# Spark-power-meter-main.net
KiCad netlist of a schematic drawn in EAGLE
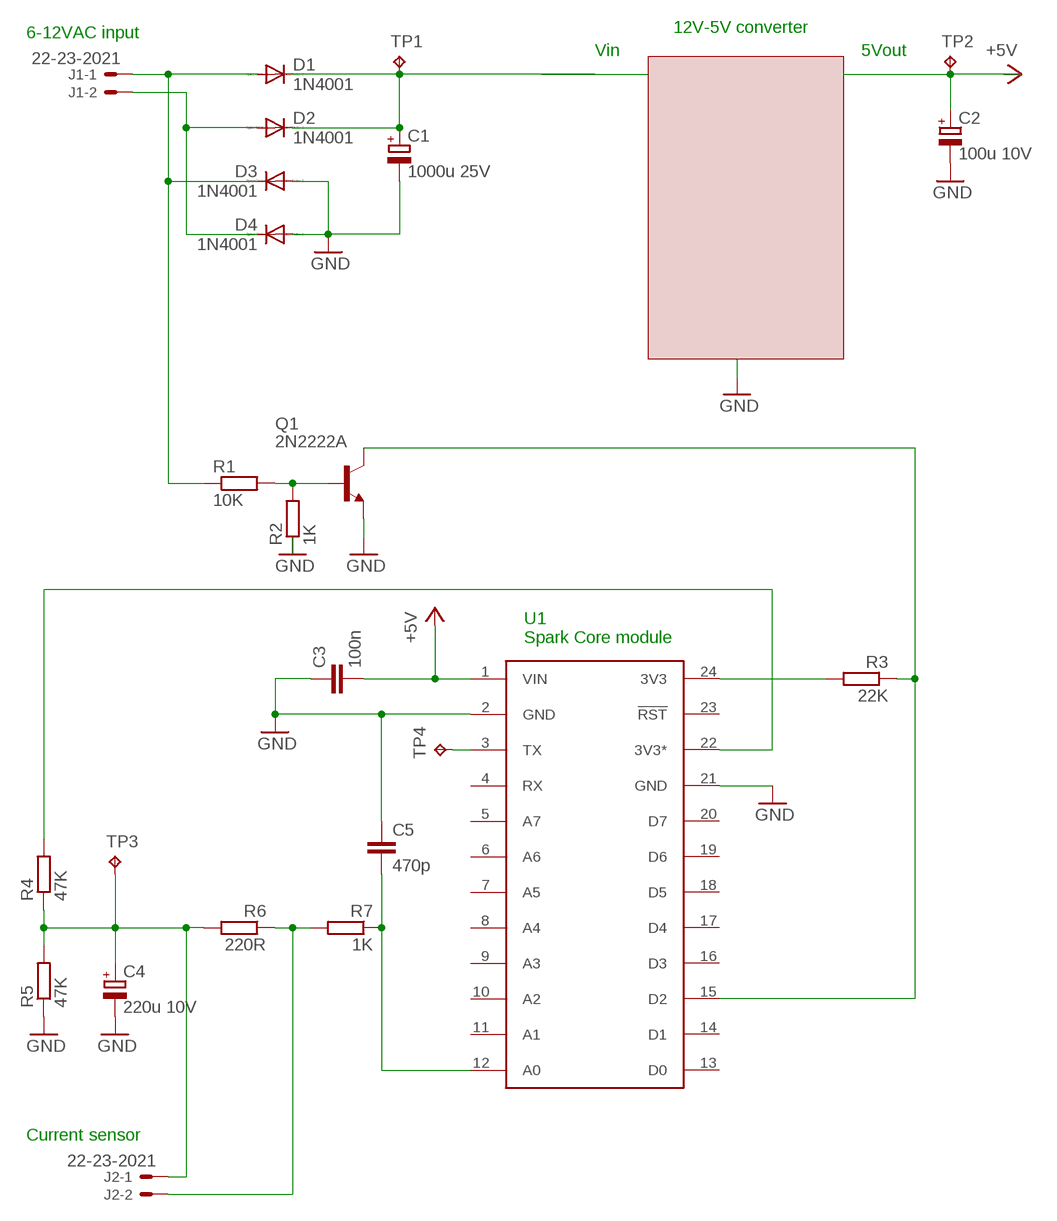
[diagram p0: schematic, sheet 1]

(export (version "E")
  (design (tool "Eeschema 10.0.6"))
  (components
    (comp (ref "C1")
      (value "1000u 25V")
      (footprint "eagle-import:E5R")
      (libsource (lib "eagle-import") (part "CPOL-EUE5-9VAXIAL"))
    )
    (comp (ref "C2")
      (value "100u 10V")
      (footprint "eagle-import:E5R")
      (libsource (lib "eagle-import") (part "CPOL-EUE5-9VAXIAL"))
    )
    (comp (ref "C3")
      (value "100n")
      (footprint "eagle-import:C075-032X103")
      (libsource (lib "eagle-import") (part "C-EU075-032X103"))
    )
    (comp (ref "C4")
      (value "220u 10V")
      (footprint "eagle-import:E5R")
      (libsource (lib "eagle-import") (part "CPOL-EUE5-9VAXIAL"))
    )
    (comp (ref "C5")
      (value "470p")
      (footprint "eagle-import:C075-032X103")
      (libsource (lib "eagle-import") (part "C-EU075-032X103"))
    )
    (comp (ref "D1")
      (value "1N4001")
      (footprint "eagle-import:DO41-10")
      (libsource (lib "eagle-import") (part "1N4004"))
    )
    (comp (ref "D2")
      (value "1N4001")
      (footprint "eagle-import:DO41-10")
      (libsource (lib "eagle-import") (part "1N4004"))
    )
    (comp (ref "D3")
      (value "1N4001")
      (footprint "eagle-import:DO41-10")
      (libsource (lib "eagle-import") (part "1N4004"))
    )
    (comp (ref "D4")
      (value "1N4001")
      (footprint "eagle-import:DO41-10")
      (libsource (lib "eagle-import") (part "1N4004"))
    )
    (comp (ref "J1")
      (value "22-23-2021")
      (footprint "eagle-import:22-23-2021")
      (fields (field (name "MF") "MOLEX"))
      (libsource (lib "eagle-import") (part "22-23-2021"))
    )
    (comp (ref "J2")
      (value "22-23-2021")
      (footprint "eagle-import:22-23-2021")
      (fields (field (name "MF") "MOLEX"))
      (libsource (lib "eagle-import") (part "22-23-2021"))
    )
    (comp (ref "Q1")
      (value "2N2222A")
      (footprint "eagle-import:TO18")
      (libsource (lib "eagle-import") (part "2N2222A"))
    )
    (comp (ref "R1")
      (value "10K")
      (footprint "eagle-import:0207_10")
      (libsource (lib "eagle-import") (part "R-EU_0207/10"))
    )
    (comp (ref "R2")
      (value "1K")
      (footprint "eagle-import:0207_10")
      (libsource (lib "eagle-import") (part "R-EU_0207/10"))
    )
    (comp (ref "R3")
      (value "22K")
      (footprint "eagle-import:0207_10")
      (libsource (lib "eagle-import") (part "R-EU_0207/10"))
    )
    (comp (ref "R4")
      (value "47K")
      (footprint "eagle-import:0207_10")
      (libsource (lib "eagle-import") (part "R-EU_0207/10"))
    )
    (comp (ref "R5")
      (value "47K")
      (footprint "eagle-import:0207_10")
      (libsource (lib "eagle-import") (part "R-EU_0207/10"))
    )
    (comp (ref "R6")
      (value "220R")
      (footprint "eagle-import:0207_10")
      (libsource (lib "eagle-import") (part "R-EU_0207/10"))
    )
    (comp (ref "R7")
      (value "1K")
      (footprint "eagle-import:0207_10")
      (libsource (lib "eagle-import") (part "R-EU_0207/10"))
    )
    (comp (ref "TP1")
      (value "TPB1,27")
      (footprint "eagle-import:B1,27")
      (libsource (lib "eagle-import") (part "TPB1,27"))
    )
    (comp (ref "TP2")
      (value "TPB1,27")
      (footprint "eagle-import:B1,27")
      (libsource (lib "eagle-import") (part "TPB1,27"))
    )
    (comp (ref "TP3")
      (value "TPB1,27")
      (footprint "eagle-import:B1,27")
      (libsource (lib "eagle-import") (part "TPB1,27"))
    )
    (comp (ref "TP4")
      (value "TPB1,27")
      (footprint "eagle-import:B1,27")
      (libsource (lib "eagle-import") (part "TPB1,27"))
    )
    (comp (ref "U$1")
      (value "SPARK_CORECORE")
      (footprint "eagle-import:SPARK_CORE")
      (libsource (lib "eagle-import") (part "SPARK_CORECORE"))
    )
  )
  (nets
    (net (code "1") (name "+5V") (class "Default")
      (node (ref "C2") (pin "+") (pinfunction "+_+") (pintype "passive"))
      (node (ref "C3") (pin "2") (pinfunction "2_2") (pintype "passive"))
      (node (ref "TP2") (pin "TP") (pinfunction "TP_TP") (pintype "input"))
      (node (ref "U$1") (pin "1") (pinfunction "VIN_1") (pintype "power_in"))
    )
    (net (code "2") (name "GND") (class "Default")
      (node (ref "C1") (pin "-") (pinfunction "-_-") (pintype "passive"))
      (node (ref "C2") (pin "-") (pinfunction "-_-") (pintype "passive"))
      (node (ref "C3") (pin "1") (pinfunction "1_1") (pintype "passive"))
      (node (ref "C4") (pin "-") (pinfunction "-_-") (pintype "passive"))
      (node (ref "C5") (pin "1") (pinfunction "1_1") (pintype "passive"))
      (node (ref "D3") (pin "A") (pinfunction "A_A") (pintype "passive"))
      (node (ref "D4") (pin "A") (pinfunction "A_A") (pintype "passive"))
      (node (ref "Q1") (pin "1") (pinfunction "E_1") (pintype "passive"))
      (node (ref "R2") (pin "1") (pinfunction "1_1") (pintype "passive"))
      (node (ref "R5") (pin "1") (pinfunction "1_1") (pintype "passive"))
      (node (ref "U$1") (pin "2") (pinfunction "GND_2") (pintype "power_in"))
      (node (ref "U$1") (pin "21") (pinfunction "GND_21") (pintype "power_in"))
    )
    (net (code "3") (name "Net-(C1-Pad+)") (class "Default")
      (node (ref "C1") (pin "+") (pinfunction "+_+") (pintype "passive"))
      (node (ref "D1") (pin "C") (pinfunction "C_C") (pintype "passive"))
      (node (ref "D2") (pin "C") (pinfunction "C_C") (pintype "passive"))
      (node (ref "TP1") (pin "TP") (pinfunction "TP_TP") (pintype "input"))
    )
    (net (code "4") (name "Net-(J1A-S)") (class "Default")
      (node (ref "D1") (pin "A") (pinfunction "A_A") (pintype "passive"))
      (node (ref "D3") (pin "C") (pinfunction "C_C") (pintype "passive"))
      (node (ref "J1") (pin "1") (pinfunction "S_1") (pintype "passive"))
      (node (ref "R1") (pin "1") (pinfunction "1_1") (pintype "passive"))
    )
    (net (code "5") (name "Net-(J1B-S)") (class "Default")
      (node (ref "D2") (pin "A") (pinfunction "A_A") (pintype "passive"))
      (node (ref "D4") (pin "C") (pinfunction "C_C") (pintype "passive"))
      (node (ref "J1") (pin "2") (pinfunction "S_2") (pintype "passive"))
    )
    (net (code "6") (name "Net-(J2A-S)") (class "Default")
      (node (ref "C4") (pin "+") (pinfunction "+_+") (pintype "passive"))
      (node (ref "J2") (pin "1") (pinfunction "S_1") (pintype "passive"))
      (node (ref "R4") (pin "1") (pinfunction "1_1") (pintype "passive"))
      (node (ref "R5") (pin "2") (pinfunction "2_2") (pintype "passive"))
      (node (ref "R6") (pin "2") (pinfunction "2_2") (pintype "passive"))
      (node (ref "TP3") (pin "TP") (pinfunction "TP_TP") (pintype "input"))
    )
    (net (code "7") (name "Net-(J2B-S)") (class "Default")
      (node (ref "J2") (pin "2") (pinfunction "S_2") (pintype "passive"))
      (node (ref "R6") (pin "1") (pinfunction "1_1") (pintype "passive"))
      (node (ref "R7") (pin "2") (pinfunction "2_2") (pintype "passive"))
    )
    (net (code "8") (name "Net-(Q1-B)") (class "Default")
      (node (ref "Q1") (pin "2") (pinfunction "B_2") (pintype "passive"))
      (node (ref "R1") (pin "2") (pinfunction "2_2") (pintype "passive"))
      (node (ref "R2") (pin "2") (pinfunction "2_2") (pintype "passive"))
    )
    (net (code "9") (name "Net-(Q1-C)") (class "Default")
      (node (ref "Q1") (pin "3") (pinfunction "C_3") (pintype "passive"))
      (node (ref "R3") (pin "1") (pinfunction "1_1") (pintype "passive"))
      (node (ref "U$1") (pin "15") (pinfunction "D2_15") (pintype "bidirectional"))
    )
    (net (code "10") (name "Net-(U$1-3V3)") (class "Default")
      (node (ref "R3") (pin "2") (pinfunction "2_2") (pintype "passive"))
      (node (ref "U$1") (pin "24") (pinfunction "3V3_24") (pintype "power_in"))
    )
    (net (code "11") (name "Net-(U$1-3V3*)") (class "Default")
      (node (ref "R4") (pin "2") (pinfunction "2_2") (pintype "passive"))
      (node (ref "U$1") (pin "22") (pinfunction "3V3*_22") (pintype "power_in"))
    )
    (net (code "12") (name "Net-(U$1-A0)") (class "Default")
      (node (ref "C5") (pin "2") (pinfunction "2_2") (pintype "passive"))
      (node (ref "R7") (pin "1") (pinfunction "1_1") (pintype "passive"))
      (node (ref "U$1") (pin "12") (pinfunction "A0_12") (pintype "bidirectional"))
    )
    (net (code "13") (name "Net-(U$1-TX)") (class "Default")
      (node (ref "TP4") (pin "TP") (pinfunction "TP_TP") (pintype "input"))
      (node (ref "U$1") (pin "3") (pinfunction "TX_3") (pintype "bidirectional"))
    )
    (net (code "14") (name "unconnected-(U$1-A1-Pad11)") (class "Default")
      (node (ref "U$1") (pin "11") (pinfunction "A1_11") (pintype "bidirectional"))
    )
    (net (code "15") (name "unconnected-(U$1-A2-Pad10)") (class "Default")
      (node (ref "U$1") (pin "10") (pinfunction "A2_10") (pintype "bidirectional"))
    )
    (net (code "16") (name "unconnected-(U$1-A3-Pad9)") (class "Default")
      (node (ref "U$1") (pin "9") (pinfunction "A3_9") (pintype "bidirectional"))
    )
    (net (code "17") (name "unconnected-(U$1-A4-Pad8)") (class "Default")
      (node (ref "U$1") (pin "8") (pinfunction "A4_8") (pintype "bidirectional"))
    )
    (net (code "18") (name "unconnected-(U$1-A5-Pad7)") (class "Default")
      (node (ref "U$1") (pin "7") (pinfunction "A5_7") (pintype "bidirectional"))
    )
    (net (code "19") (name "unconnected-(U$1-A6-Pad6)") (class "Default")
      (node (ref "U$1") (pin "6") (pinfunction "A6_6") (pintype "bidirectional"))
    )
    (net (code "20") (name "unconnected-(U$1-A7-Pad5)") (class "Default")
      (node (ref "U$1") (pin "5") (pinfunction "A7_5") (pintype "bidirectional"))
    )
    (net (code "21") (name "unconnected-(U$1-D0-Pad13)") (class "Default")
      (node (ref "U$1") (pin "13") (pinfunction "D0_13") (pintype "bidirectional"))
    )
    (net (code "22") (name "unconnected-(U$1-D1-Pad14)") (class "Default")
      (node (ref "U$1") (pin "14") (pinfunction "D1_14") (pintype "bidirectional"))
    )
    (net (code "23") (name "unconnected-(U$1-D3-Pad16)") (class "Default")
      (node (ref "U$1") (pin "16") (pinfunction "D3_16") (pintype "bidirectional"))
    )
    (net (code "24") (name "unconnected-(U$1-D4-Pad17)") (class "Default")
      (node (ref "U$1") (pin "17") (pinfunction "D4_17") (pintype "bidirectional"))
    )
    (net (code "25") (name "unconnected-(U$1-D5-Pad18)") (class "Default")
      (node (ref "U$1") (pin "18") (pinfunction "D5_18") (pintype "bidirectional"))
    )
    (net (code "26") (name "unconnected-(U$1-D6-Pad19)") (class "Default")
      (node (ref "U$1") (pin "19") (pinfunction "D6_19") (pintype "bidirectional"))
    )
    (net (code "27") (name "unconnected-(U$1-D7-Pad20)") (class "Default")
      (node (ref "U$1") (pin "20") (pinfunction "D7_20") (pintype "bidirectional"))
    )
    (net (code "28") (name "unconnected-(U$1-RX-Pad4)") (class "Default")
      (node (ref "U$1") (pin "4") (pinfunction "RX_4") (pintype "bidirectional"))
    )
    (net (code "29") (name "unconnected-(U$1-~{RST}-Pad23)") (class "Default")
      (node (ref "U$1") (pin "23") (pinfunction "~{RST}_23") (pintype "bidirectional"))
    )
  )
)
